# Sound.net
KiCad netlist of a schematic drawn in EAGLE
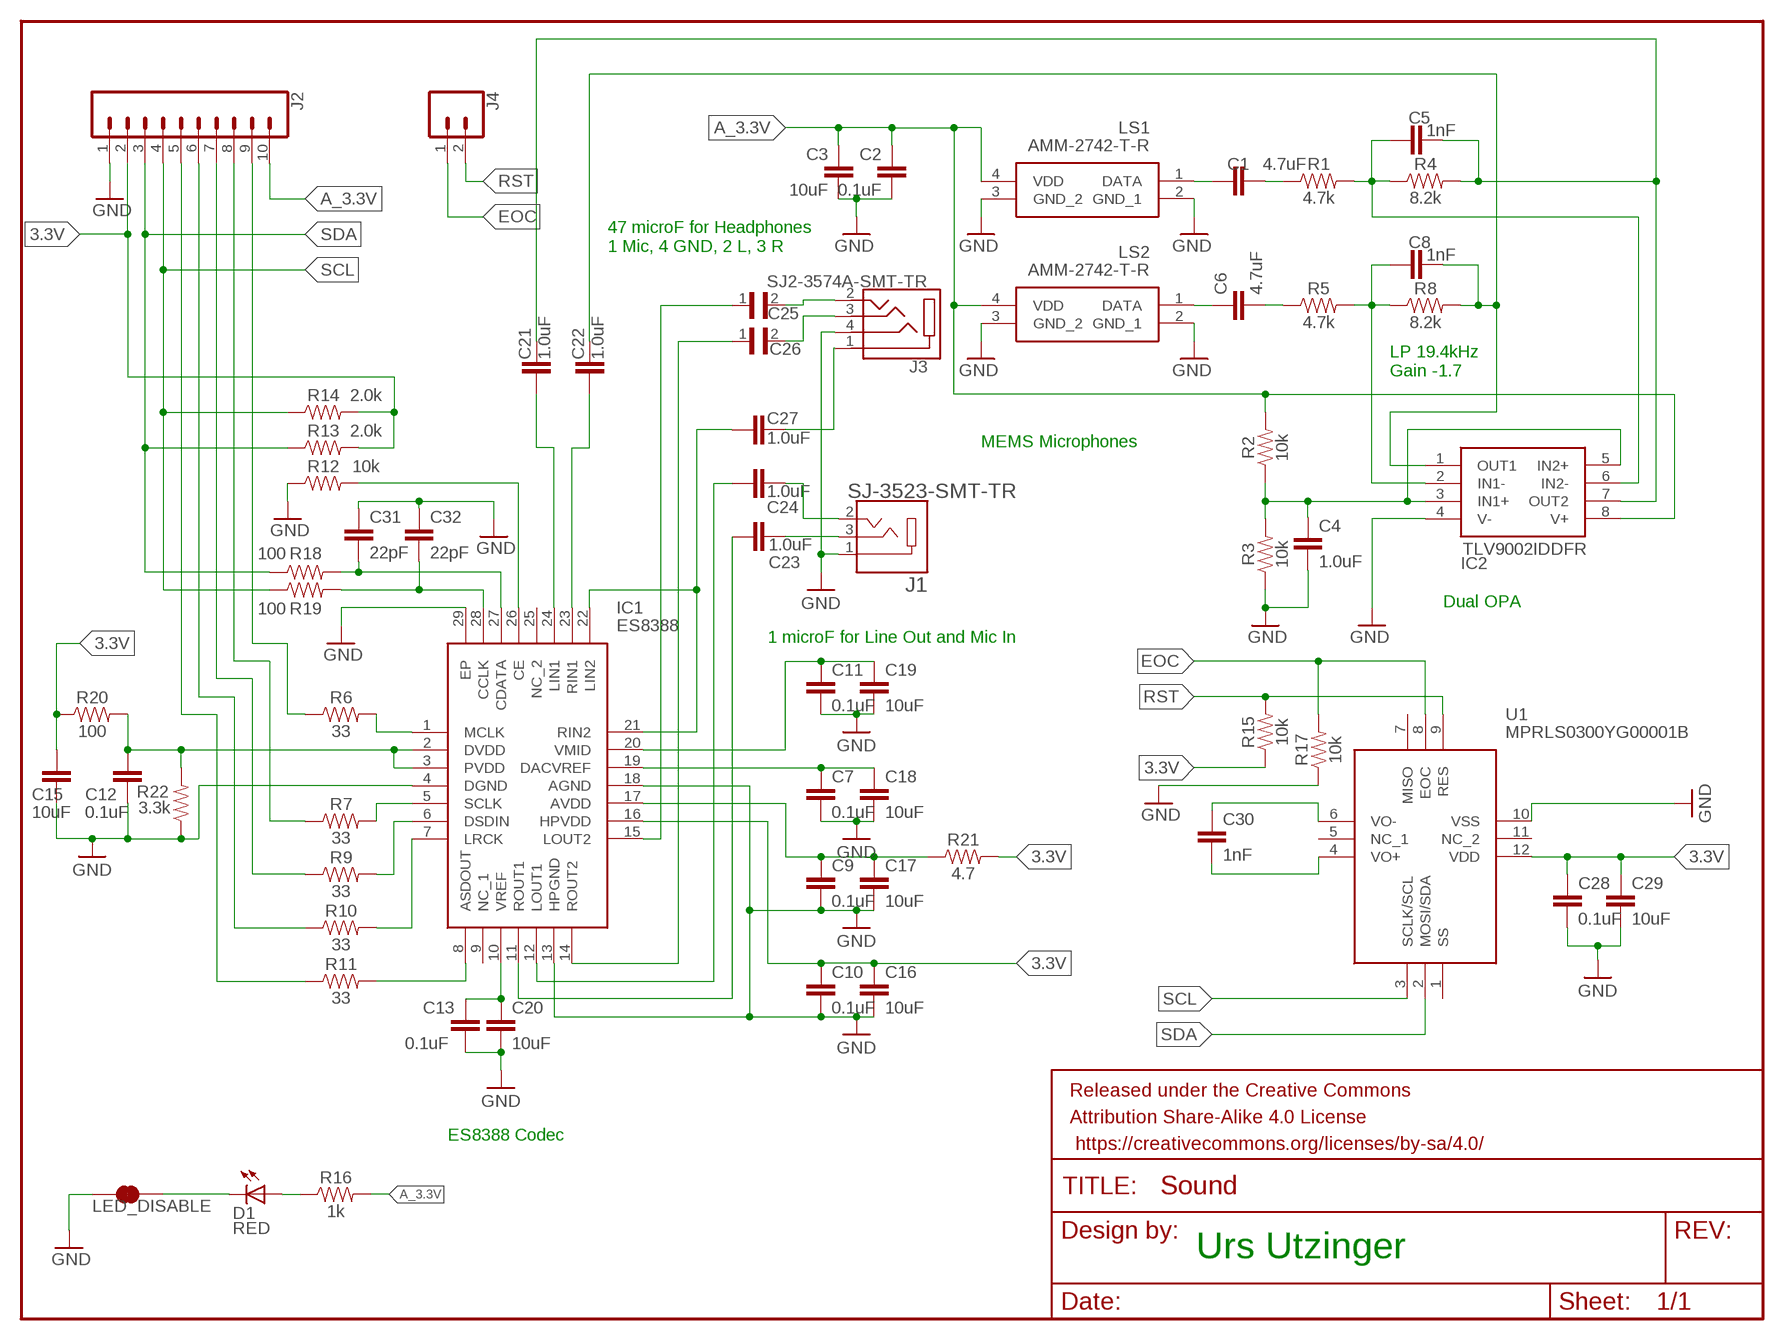
[diagram p0: schematic, sheet 1]

(export (version "E")
  (design (tool "Eeschema 10.0.6"))
  (components
    (comp (ref "C1")
      (value "4.7uF")
      (footprint "eagle-import:0603")
      (libsource (lib "eagle-import") (part "4.7UF-0603-6.3V-(10%)"))
    )
    (comp (ref "C2")
      (value "0.1uF")
      (footprint "eagle-import:0603")
      (libsource (lib "eagle-import") (part "0.1UF-0603-25V-5%"))
    )
    (comp (ref "C3")
      (value "10uF")
      (footprint "eagle-import:0603")
      (libsource (lib "eagle-import") (part "10UF-0603-6.3V-20%"))
    )
    (comp (ref "C4")
      (value "1.0uF")
      (footprint "eagle-import:0603")
      (libsource (lib "eagle-import") (part "1.0UF-0603-16V-10%"))
    )
    (comp (ref "C5")
      (value "1nF")
      (footprint "eagle-import:0603")
      (libsource (lib "eagle-import") (part "1.0NF/1000PF-0603-50V-10%"))
    )
    (comp (ref "C6")
      (value "4.7uF")
      (footprint "eagle-import:0603")
      (libsource (lib "eagle-import") (part "4.7UF-0603-6.3V-(10%)"))
    )
    (comp (ref "C7")
      (value "0.1uF")
      (footprint "eagle-import:0603")
      (libsource (lib "eagle-import") (part "0.1UF-0603-25V-5%"))
    )
    (comp (ref "C8")
      (value "1nF")
      (footprint "eagle-import:0603")
      (libsource (lib "eagle-import") (part "1.0NF/1000PF-0603-50V-10%"))
    )
    (comp (ref "C9")
      (value "0.1uF")
      (footprint "eagle-import:0603")
      (libsource (lib "eagle-import") (part "0.1UF-0603-25V-5%"))
    )
    (comp (ref "C10")
      (value "0.1uF")
      (footprint "eagle-import:0603")
      (libsource (lib "eagle-import") (part "0.1UF-0603-25V-5%"))
    )
    (comp (ref "C11")
      (value "0.1uF")
      (footprint "eagle-import:0603")
      (libsource (lib "eagle-import") (part "0.1UF-0603-25V-5%"))
    )
    (comp (ref "C12")
      (value "0.1uF")
      (footprint "eagle-import:0603")
      (libsource (lib "eagle-import") (part "0.1UF-0603-25V-5%"))
    )
    (comp (ref "C13")
      (value "0.1uF")
      (footprint "eagle-import:0603")
      (libsource (lib "eagle-import") (part "0.1UF-0603-25V-5%"))
    )
    (comp (ref "C15")
      (value "10uF")
      (footprint "eagle-import:0603")
      (libsource (lib "eagle-import") (part "10UF-0603-6.3V-20%"))
    )
    (comp (ref "C16")
      (value "10uF")
      (footprint "eagle-import:0603")
      (libsource (lib "eagle-import") (part "10UF-0603-6.3V-20%"))
    )
    (comp (ref "C17")
      (value "10uF")
      (footprint "eagle-import:0603")
      (libsource (lib "eagle-import") (part "10UF-0603-6.3V-20%"))
    )
    (comp (ref "C18")
      (value "10uF")
      (footprint "eagle-import:0603")
      (libsource (lib "eagle-import") (part "10UF-0603-6.3V-20%"))
    )
    (comp (ref "C19")
      (value "10uF")
      (footprint "eagle-import:0603")
      (libsource (lib "eagle-import") (part "10UF-0603-6.3V-20%"))
    )
    (comp (ref "C20")
      (value "10uF")
      (footprint "eagle-import:0603")
      (libsource (lib "eagle-import") (part "10UF-0603-6.3V-20%"))
    )
    (comp (ref "C21")
      (value "1.0uF")
      (footprint "eagle-import:0603")
      (libsource (lib "eagle-import") (part "1.0UF-0603-16V-10%"))
    )
    (comp (ref "C22")
      (value "1.0uF")
      (footprint "eagle-import:0603")
      (libsource (lib "eagle-import") (part "1.0UF-0603-16V-10%"))
    )
    (comp (ref "C23")
      (value "1.0uF")
      (footprint "eagle-import:0603")
      (libsource (lib "eagle-import") (part "1.0UF-0603-16V-10%"))
    )
    (comp (ref "C24")
      (value "1.0uF")
      (footprint "eagle-import:0603")
      (libsource (lib "eagle-import") (part "1.0UF-0603-16V-10%"))
    )
    (comp (ref "C25")
      (value "GRM188R60J476ME15D")
      (footprint "eagle-import:CAPC1608X100N")
      (libsource (lib "eagle-import") (part "GRM188R60J476ME15D"))
    )
    (comp (ref "C26")
      (value "GRM188R60J476ME15D")
      (footprint "eagle-import:CAPC1608X100N")
      (libsource (lib "eagle-import") (part "GRM188R60J476ME15D"))
    )
    (comp (ref "C27")
      (value "1.0uF")
      (footprint "eagle-import:0603")
      (libsource (lib "eagle-import") (part "1.0UF-0603-16V-10%"))
    )
    (comp (ref "C28")
      (value "0.1uF")
      (footprint "eagle-import:0603")
      (libsource (lib "eagle-import") (part "0.1UF-0603-25V-5%"))
    )
    (comp (ref "C29")
      (value "10uF")
      (footprint "eagle-import:0603")
      (libsource (lib "eagle-import") (part "10UF-0603-6.3V-20%"))
    )
    (comp (ref "C30")
      (value "1nF")
      (footprint "eagle-import:0603")
      (libsource (lib "eagle-import") (part "1.0NF/1000PF-0603-50V-10%"))
    )
    (comp (ref "C31")
      (value "22pF")
      (footprint "eagle-import:0603")
      (libsource (lib "eagle-import") (part "22PF-0603-50V-5%"))
    )
    (comp (ref "C32")
      (value "22pF")
      (footprint "eagle-import:0603")
      (libsource (lib "eagle-import") (part "22PF-0603-50V-5%"))
    )
    (comp (ref "D1")
      (value "RED")
      (footprint "eagle-import:LED-0603")
      (libsource (lib "eagle-import") (part "LED-RED0603"))
    )
    (comp (ref "FRAME1")
      (value "FRAME-LETTERNO_PACKAGE")
      (footprint "eagle-import:DUMMY")
      (fields (field (name "DESIGNER") "Nobody"))
      (libsource (lib "eagle-import") (part "FRAME-LETTERNO_PACKAGE"))
    )
    (comp (ref "IC1")
      (value "ES8388")
      (footprint "eagle-import:QFN45P400X400X90-29N")
      (libsource (lib "eagle-import") (part "ES8388"))
    )
    (comp (ref "IC2")
      (value "TLV9002IDDFR")
      (footprint "eagle-import:SOT65P280X110-8N")
      (fields (field (name "MOUSER_PART_NUMBER") "595-TLV9002IDDFR"))
      (libsource (lib "eagle-import") (part "TLV9002IDDFR"))
    )
    (comp (ref "J1")
      (value "SJ-3523-SMT-TR")
      (footprint "eagle-import:CUI_SJ-3523-SMT-TR")
      (fields (field (name "MF") "CUI Inc"))
      (libsource (lib "eagle-import") (part "SJ-3523-SMT-TR"))
    )
    (comp (ref "J2")
      (value "CONN_10\"")
      (footprint "eagle-import:1X10")
      (libsource (lib "eagle-import") (part "CONN_10{dblquote}"))
    )
    (comp (ref "J3")
      (value "SJ2-3574A-SMT-TR")
      (footprint "eagle-import:CUI_SJ2-3574A-SMT-TR")
      (fields (field (name "MANUFACTURER") "CUI"))
      (libsource (lib "eagle-import") (part "SJ2-3574A-SMT-TR"))
    )
    (comp (ref "J4")
      (value "CONN_02")
      (footprint "eagle-import:1X02")
      (libsource (lib "eagle-import") (part "CONN_02"))
    )
    (comp (ref "LED_DISABLE")
      (value "JUMPER-SMT_2_NC_TRACE_SILK")
      (footprint "eagle-import:SMT-JUMPER_2_NC_TRACE_SILK")
      (libsource (lib "eagle-import") (part "JUMPER-SMT_2_NC_TRACE_SILK"))
    )
    (comp (ref "LS1")
      (value "AMM-2742-T-R")
      (footprint "eagle-import:AMM2742TR")
      (fields (field (name "MOUSER_PART_NUMBER") "665-AMM-2742-T-R"))
      (libsource (lib "eagle-import") (part "AMM-2742-T-R"))
    )
    (comp (ref "LS2")
      (value "AMM-2742-T-R")
      (footprint "eagle-import:AMM2742TR")
      (fields (field (name "MOUSER_PART_NUMBER") "665-AMM-2742-T-R"))
      (libsource (lib "eagle-import") (part "AMM-2742-T-R"))
    )
    (comp (ref "R1")
      (value "4.7k")
      (footprint "eagle-import:0603")
      (libsource (lib "eagle-import") (part "4.7KOHM-0603-1/10W-1%"))
    )
    (comp (ref "R2")
      (value "10k")
      (footprint "eagle-import:0603")
      (libsource (lib "eagle-import") (part "10KOHM-0603-1/10W-1%"))
    )
    (comp (ref "R3")
      (value "10k")
      (footprint "eagle-import:0603")
      (libsource (lib "eagle-import") (part "10KOHM-0603-1/10W-1%"))
    )
    (comp (ref "R4")
      (value "8.2k")
      (footprint "eagle-import:0603")
      (libsource (lib "eagle-import") (part "8.2KOHM-0603-1/10W-5%"))
    )
    (comp (ref "R5")
      (value "4.7k")
      (footprint "eagle-import:0603")
      (libsource (lib "eagle-import") (part "4.7KOHM-0603-1/10W-1%"))
    )
    (comp (ref "R6")
      (value "33")
      (footprint "eagle-import:0603")
      (libsource (lib "eagle-import") (part "33OHM-0603-1/10W-1%"))
    )
    (comp (ref "R7")
      (value "33")
      (footprint "eagle-import:0603")
      (libsource (lib "eagle-import") (part "33OHM-0603-1/10W-1%"))
    )
    (comp (ref "R8")
      (value "8.2k")
      (footprint "eagle-import:0603")
      (libsource (lib "eagle-import") (part "8.2KOHM-0603-1/10W-5%"))
    )
    (comp (ref "R9")
      (value "33")
      (footprint "eagle-import:0603")
      (libsource (lib "eagle-import") (part "33OHM-0603-1/10W-1%"))
    )
    (comp (ref "R10")
      (value "33")
      (footprint "eagle-import:0603")
      (libsource (lib "eagle-import") (part "33OHM-0603-1/10W-1%"))
    )
    (comp (ref "R11")
      (value "33")
      (footprint "eagle-import:0603")
      (libsource (lib "eagle-import") (part "33OHM-0603-1/10W-1%"))
    )
    (comp (ref "R12")
      (value "10k")
      (footprint "eagle-import:0603")
      (libsource (lib "eagle-import") (part "10KOHM-0603-1/10W-1%"))
    )
    (comp (ref "R13")
      (value "2.0k")
      (footprint "eagle-import:0603")
      (libsource (lib "eagle-import") (part "2.0KOHM-0603-1/10W-5%"))
    )
    (comp (ref "R14")
      (value "2.0k")
      (footprint "eagle-import:0603")
      (libsource (lib "eagle-import") (part "2.0KOHM-0603-1/10W-5%"))
    )
    (comp (ref "R15")
      (value "10k")
      (footprint "eagle-import:0603")
      (libsource (lib "eagle-import") (part "10KOHM-0603-1/10W-1%"))
    )
    (comp (ref "R16")
      (value "1k")
      (footprint "eagle-import:0603")
      (libsource (lib "eagle-import") (part "1KOHM-0603-1/10W-1%"))
    )
    (comp (ref "R17")
      (value "10k")
      (footprint "eagle-import:0603")
      (libsource (lib "eagle-import") (part "10KOHM-0603-1/10W-1%"))
    )
    (comp (ref "R18")
      (value "100")
      (footprint "eagle-import:0603")
      (libsource (lib "eagle-import") (part "100OHM-0603-1/10W-1%"))
    )
    (comp (ref "R19")
      (value "100")
      (footprint "eagle-import:0603")
      (libsource (lib "eagle-import") (part "100OHM-0603-1/10W-1%"))
    )
    (comp (ref "R20")
      (value "100")
      (footprint "eagle-import:0603")
      (libsource (lib "eagle-import") (part "100OHM-0603-1/10W-1%"))
    )
    (comp (ref "R21")
      (value "4.7")
      (footprint "eagle-import:0603")
      (libsource (lib "eagle-import") (part "4.7OHM-0603-1/10W-1%"))
    )
    (comp (ref "R22")
      (value "3.3k")
      (footprint "eagle-import:0603")
      (libsource (lib "eagle-import") (part "3.3KOHM-0603-1/10W-1%"))
    )
    (comp (ref "U1")
      (value "MPRLS0300YG00001B")
      (footprint "eagle-import:MPRLS0300YG00001B")
      (fields (field (name "MOUSER_PART_NUMBER") "785-MPRLS0300YG0001B"))
      (libsource (lib "eagle-import") (part "MPRLS0300YG00001B"))
    )
  )
  (nets
    (net (code "1") (name "3.3V") (class "Default")
      (node (ref "C10") (pin "1") (pinfunction "1_1") (pintype "passive"))
      (node (ref "C15") (pin "1") (pinfunction "1_1") (pintype "passive"))
      (node (ref "C16") (pin "1") (pinfunction "1_1") (pintype "passive"))
      (node (ref "C28") (pin "1") (pinfunction "1_1") (pintype "passive"))
      (node (ref "C29") (pin "1") (pinfunction "1_1") (pintype "passive"))
      (node (ref "IC1") (pin "16") (pinfunction "HPVDD_16") (pintype "bidirectional"))
      (node (ref "J2") (pin "2") (pinfunction "2_2") (pintype "passive"))
      (node (ref "R13") (pin "2") (pinfunction "2_2") (pintype "passive"))
      (node (ref "R14") (pin "2") (pinfunction "2_2") (pintype "passive"))
      (node (ref "R15") (pin "1") (pinfunction "1_1") (pintype "passive"))
      (node (ref "R20") (pin "1") (pinfunction "1_1") (pintype "passive"))
      (node (ref "R21") (pin "2") (pinfunction "2_2") (pintype "passive"))
      (node (ref "U1") (pin "12") (pinfunction "VDD_12") (pintype "bidirectional"))
    )
    (net (code "2") (name "A_3.3V") (class "Default")
      (node (ref "C2") (pin "1") (pinfunction "1_1") (pintype "passive"))
      (node (ref "C3") (pin "1") (pinfunction "1_1") (pintype "passive"))
      (node (ref "IC2") (pin "8") (pinfunction "V+_8") (pintype "bidirectional"))
      (node (ref "J2") (pin "10") (pinfunction "10_10") (pintype "passive"))
      (node (ref "LS1") (pin "4") (pinfunction "VDD_4") (pintype "bidirectional"))
      (node (ref "LS2") (pin "4") (pinfunction "VDD_4") (pintype "bidirectional"))
      (node (ref "R16") (pin "2") (pinfunction "2_2") (pintype "passive"))
      (node (ref "R2") (pin "2") (pinfunction "2_2") (pintype "passive"))
    )
    (net (code "3") (name "EOC") (class "Default")
      (node (ref "J4") (pin "1") (pinfunction "1_1") (pintype "passive"))
      (node (ref "R17") (pin "2") (pinfunction "2_2") (pintype "passive"))
      (node (ref "U1") (pin "8") (pinfunction "EOC_8") (pintype "bidirectional"))
    )
    (net (code "4") (name "GND") (class "Default")
      (node (ref "C10") (pin "2") (pinfunction "2_2") (pintype "passive"))
      (node (ref "C11") (pin "2") (pinfunction "2_2") (pintype "passive"))
      (node (ref "C12") (pin "2") (pinfunction "2_2") (pintype "passive"))
      (node (ref "C13") (pin "2") (pinfunction "2_2") (pintype "passive"))
      (node (ref "C15") (pin "2") (pinfunction "2_2") (pintype "passive"))
      (node (ref "C16") (pin "2") (pinfunction "2_2") (pintype "passive"))
      (node (ref "C17") (pin "2") (pinfunction "2_2") (pintype "passive"))
      (node (ref "C18") (pin "2") (pinfunction "2_2") (pintype "passive"))
      (node (ref "C19") (pin "2") (pinfunction "2_2") (pintype "passive"))
      (node (ref "C2") (pin "2") (pinfunction "2_2") (pintype "passive"))
      (node (ref "C20") (pin "2") (pinfunction "2_2") (pintype "passive"))
      (node (ref "C28") (pin "2") (pinfunction "2_2") (pintype "passive"))
      (node (ref "C29") (pin "2") (pinfunction "2_2") (pintype "passive"))
      (node (ref "C3") (pin "2") (pinfunction "2_2") (pintype "passive"))
      (node (ref "C31") (pin "1") (pinfunction "1_1") (pintype "passive"))
      (node (ref "C32") (pin "1") (pinfunction "1_1") (pintype "passive"))
      (node (ref "C4") (pin "2") (pinfunction "2_2") (pintype "passive"))
      (node (ref "C7") (pin "2") (pinfunction "2_2") (pintype "passive"))
      (node (ref "C9") (pin "2") (pinfunction "2_2") (pintype "passive"))
      (node (ref "IC1") (pin "13") (pinfunction "HPGND_13") (pintype "bidirectional"))
      (node (ref "IC1") (pin "18") (pinfunction "AGND_18") (pintype "bidirectional"))
      (node (ref "IC1") (pin "29") (pinfunction "EP_29") (pintype "bidirectional"))
      (node (ref "IC1") (pin "4") (pinfunction "DGND_4") (pintype "bidirectional"))
      (node (ref "IC2") (pin "4") (pinfunction "V-_4") (pintype "bidirectional"))
      (node (ref "J1") (pin "1") (pinfunction "1_1") (pintype "passive"))
      (node (ref "J2") (pin "1") (pinfunction "1_1") (pintype "passive"))
      (node (ref "J3") (pin "4") (pinfunction "4_4") (pintype "passive"))
      (node (ref "LED_DISABLE") (pin "1") (pinfunction "1_1") (pintype "passive"))
      (node (ref "LS1") (pin "2") (pinfunction "GND_1_2") (pintype "bidirectional"))
      (node (ref "LS1") (pin "3") (pinfunction "GND_2_3") (pintype "bidirectional"))
      (node (ref "LS2") (pin "2") (pinfunction "GND_1_2") (pintype "bidirectional"))
      (node (ref "LS2") (pin "3") (pinfunction "GND_2_3") (pintype "bidirectional"))
      (node (ref "R12") (pin "1") (pinfunction "1_1") (pintype "passive"))
      (node (ref "R17") (pin "1") (pinfunction "1_1") (pintype "passive"))
      (node (ref "R22") (pin "1") (pinfunction "1_1") (pintype "passive"))
      (node (ref "R3") (pin "1") (pinfunction "1_1") (pintype "passive"))
      (node (ref "U1") (pin "10") (pinfunction "VSS_10") (pintype "bidirectional"))
    )
    (net (code "5") (name "Net-(C1-Pad2)") (class "Default")
      (node (ref "C1") (pin "2") (pinfunction "2_2") (pintype "passive"))
      (node (ref "R1") (pin "1") (pinfunction "1_1") (pintype "passive"))
    )
    (net (code "6") (name "Net-(C6-Pad2)") (class "Default")
      (node (ref "C6") (pin "2") (pinfunction "2_2") (pintype "passive"))
      (node (ref "R5") (pin "1") (pinfunction "1_1") (pintype "passive"))
    )
    (net (code "7") (name "Net-(C23-Pad1)") (class "Default")
      (node (ref "C23") (pin "1") (pinfunction "1_1") (pintype "passive"))
      (node (ref "J1") (pin "3") (pinfunction "3_3") (pintype "passive"))
    )
    (net (code "8") (name "Net-(C24-Pad1)") (class "Default")
      (node (ref "C24") (pin "1") (pinfunction "1_1") (pintype "passive"))
      (node (ref "J1") (pin "2") (pinfunction "2_2") (pintype "passive"))
    )
    (net (code "9") (name "Net-(C25-Pad2)") (class "Default")
      (node (ref "C25") (pin "2") (pinfunction "2_2") (pintype "passive"))
      (node (ref "J3") (pin "2") (pinfunction "2_2") (pintype "passive"))
    )
    (net (code "10") (name "Net-(C26-Pad2)") (class "Default")
      (node (ref "C26") (pin "2") (pinfunction "2_2") (pintype "passive"))
      (node (ref "J3") (pin "3") (pinfunction "3_3") (pintype "passive"))
    )
    (net (code "11") (name "Net-(C27-Pad2)") (class "Default")
      (node (ref "C27") (pin "2") (pinfunction "2_2") (pintype "passive"))
      (node (ref "J3") (pin "1") (pinfunction "1_1") (pintype "passive"))
    )
    (net (code "12") (name "Net-(D1-PadA)") (class "Default")
      (node (ref "D1") (pin "A") (pinfunction "A_A") (pintype "passive"))
      (node (ref "R16") (pin "1") (pinfunction "1_1") (pintype "passive"))
    )
    (net (code "13") (name "Net-(D1-PadC)") (class "Default")
      (node (ref "D1") (pin "C") (pinfunction "C_C") (pintype "passive"))
      (node (ref "LED_DISABLE") (pin "2") (pinfunction "2_2") (pintype "passive"))
    )
    (net (code "14") (name "Net-(IC1-ASDOUT)") (class "Default")
      (node (ref "IC1") (pin "8") (pinfunction "ASDOUT_8") (pintype "bidirectional"))
      (node (ref "R11") (pin "2") (pinfunction "2_2") (pintype "passive"))
    )
    (net (code "15") (name "Net-(IC1-AVDD)") (class "Default")
      (node (ref "C17") (pin "1") (pinfunction "1_1") (pintype "passive"))
      (node (ref "C9") (pin "1") (pinfunction "1_1") (pintype "passive"))
      (node (ref "IC1") (pin "17") (pinfunction "AVDD_17") (pintype "bidirectional"))
      (node (ref "R21") (pin "1") (pinfunction "1_1") (pintype "passive"))
    )
    (net (code "16") (name "Net-(IC1-CCLK)") (class "Default")
      (node (ref "C32") (pin "2") (pinfunction "2_2") (pintype "passive"))
      (node (ref "IC1") (pin "28") (pinfunction "CCLK_28") (pintype "bidirectional"))
      (node (ref "R19") (pin "2") (pinfunction "2_2") (pintype "passive"))
    )
    (net (code "17") (name "Net-(IC1-CDATA)") (class "Default")
      (node (ref "C31") (pin "2") (pinfunction "2_2") (pintype "passive"))
      (node (ref "IC1") (pin "27") (pinfunction "CDATA_27") (pintype "bidirectional"))
      (node (ref "R18") (pin "2") (pinfunction "2_2") (pintype "passive"))
    )
    (net (code "18") (name "Net-(IC1-CE)") (class "Default")
      (node (ref "IC1") (pin "26") (pinfunction "CE_26") (pintype "bidirectional"))
      (node (ref "R12") (pin "2") (pinfunction "2_2") (pintype "passive"))
    )
    (net (code "19") (name "Net-(IC1-DACVREF)") (class "Default")
      (node (ref "C18") (pin "1") (pinfunction "1_1") (pintype "passive"))
      (node (ref "C7") (pin "1") (pinfunction "1_1") (pintype "passive"))
      (node (ref "IC1") (pin "19") (pinfunction "DACVREF_19") (pintype "bidirectional"))
    )
    (net (code "20") (name "Net-(IC1-DSDIN)") (class "Default")
      (node (ref "IC1") (pin "6") (pinfunction "DSDIN_6") (pintype "bidirectional"))
      (node (ref "R9") (pin "2") (pinfunction "2_2") (pintype "passive"))
    )
    (net (code "21") (name "Net-(IC1-DVDD)") (class "Default")
      (node (ref "C12") (pin "1") (pinfunction "1_1") (pintype "passive"))
      (node (ref "IC1") (pin "2") (pinfunction "DVDD_2") (pintype "bidirectional"))
      (node (ref "IC1") (pin "3") (pinfunction "PVDD_3") (pintype "bidirectional"))
      (node (ref "R20") (pin "2") (pinfunction "2_2") (pintype "passive"))
      (node (ref "R22") (pin "2") (pinfunction "2_2") (pintype "passive"))
    )
    (net (code "22") (name "Net-(IC1-LIN1)") (class "Default")
      (node (ref "C21") (pin "1") (pinfunction "1_1") (pintype "passive"))
      (node (ref "IC1") (pin "24") (pinfunction "LIN1_24") (pintype "bidirectional"))
    )
    (net (code "23") (name "Net-(IC1-LIN2)") (class "Default")
      (node (ref "C27") (pin "1") (pinfunction "1_1") (pintype "passive"))
      (node (ref "IC1") (pin "21") (pinfunction "RIN2_21") (pintype "bidirectional"))
      (node (ref "IC1") (pin "22") (pinfunction "LIN2_22") (pintype "bidirectional"))
    )
    (net (code "24") (name "Net-(IC1-LOUT1)") (class "Default")
      (node (ref "C24") (pin "2") (pinfunction "2_2") (pintype "passive"))
      (node (ref "IC1") (pin "12") (pinfunction "LOUT1_12") (pintype "bidirectional"))
    )
    (net (code "25") (name "Net-(IC1-LOUT2)") (class "Default")
      (node (ref "C25") (pin "1") (pinfunction "1_1") (pintype "passive"))
      (node (ref "IC1") (pin "15") (pinfunction "LOUT2_15") (pintype "bidirectional"))
    )
    (net (code "26") (name "Net-(IC1-LRCK)") (class "Default")
      (node (ref "IC1") (pin "7") (pinfunction "LRCK_7") (pintype "bidirectional"))
      (node (ref "R10") (pin "2") (pinfunction "2_2") (pintype "passive"))
    )
    (net (code "27") (name "Net-(IC1-MCLK)") (class "Default")
      (node (ref "IC1") (pin "1") (pinfunction "MCLK_1") (pintype "bidirectional"))
      (node (ref "R6") (pin "2") (pinfunction "2_2") (pintype "passive"))
    )
    (net (code "28") (name "Net-(IC1-RIN1)") (class "Default")
      (node (ref "C22") (pin "1") (pinfunction "1_1") (pintype "passive"))
      (node (ref "IC1") (pin "23") (pinfunction "RIN1_23") (pintype "bidirectional"))
    )
    (net (code "29") (name "Net-(IC1-ROUT1)") (class "Default")
      (node (ref "C23") (pin "2") (pinfunction "2_2") (pintype "passive"))
      (node (ref "IC1") (pin "11") (pinfunction "ROUT1_11") (pintype "bidirectional"))
    )
    (net (code "30") (name "Net-(IC1-ROUT2)") (class "Default")
      (node (ref "C26") (pin "1") (pinfunction "1_1") (pintype "passive"))
      (node (ref "IC1") (pin "14") (pinfunction "ROUT2_14") (pintype "bidirectional"))
    )
    (net (code "31") (name "Net-(IC1-SCLK)") (class "Default")
      (node (ref "IC1") (pin "5") (pinfunction "SCLK_5") (pintype "bidirectional"))
      (node (ref "R7") (pin "2") (pinfunction "2_2") (pintype "passive"))
    )
    (net (code "32") (name "Net-(IC1-VMID)") (class "Default")
      (node (ref "C11") (pin "1") (pinfunction "1_1") (pintype "passive"))
      (node (ref "C19") (pin "1") (pinfunction "1_1") (pintype "passive"))
      (node (ref "IC1") (pin "20") (pinfunction "VMID_20") (pintype "bidirectional"))
    )
    (net (code "33") (name "Net-(IC1-VREF)") (class "Default")
      (node (ref "C13") (pin "1") (pinfunction "1_1") (pintype "passive"))
      (node (ref "C20") (pin "1") (pinfunction "1_1") (pintype "passive"))
      (node (ref "IC1") (pin "10") (pinfunction "VREF_10") (pintype "bidirectional"))
    )
    (net (code "34") (name "Net-(IC2-IN1+)") (class "Default")
      (node (ref "C4") (pin "1") (pinfunction "1_1") (pintype "passive"))
      (node (ref "IC2") (pin "3") (pinfunction "IN1+_3") (pintype "bidirectional"))
      (node (ref "IC2") (pin "5") (pinfunction "IN2+_5") (pintype "bidirectional"))
      (node (ref "R2") (pin "1") (pinfunction "1_1") (pintype "passive"))
      (node (ref "R3") (pin "2") (pinfunction "2_2") (pintype "passive"))
    )
    (net (code "35") (name "Net-(IC2-IN1-)") (class "Default")
      (node (ref "C8") (pin "1") (pinfunction "1_1") (pintype "passive"))
      (node (ref "IC2") (pin "2") (pinfunction "IN1-_2") (pintype "bidirectional"))
      (node (ref "R5") (pin "2") (pinfunction "2_2") (pintype "passive"))
      (node (ref "R8") (pin "1") (pinfunction "1_1") (pintype "passive"))
    )
    (net (code "36") (name "Net-(IC2-IN2-)") (class "Default")
      (node (ref "C5") (pin "1") (pinfunction "1_1") (pintype "passive"))
      (node (ref "IC2") (pin "6") (pinfunction "IN2-_6") (pintype "bidirectional"))
      (node (ref "R1") (pin "2") (pinfunction "2_2") (pintype "passive"))
      (node (ref "R4") (pin "1") (pinfunction "1_1") (pintype "passive"))
    )
    (net (code "37") (name "Net-(IC2-OUT1)") (class "Default")
      (node (ref "C22") (pin "2") (pinfunction "2_2") (pintype "passive"))
      (node (ref "C8") (pin "2") (pinfunction "2_2") (pintype "passive"))
      (node (ref "IC2") (pin "1") (pinfunction "OUT1_1") (pintype "bidirectional"))
      (node (ref "R8") (pin "2") (pinfunction "2_2") (pintype "passive"))
    )
    (net (code "38") (name "Net-(IC2-OUT2)") (class "Default")
      (node (ref "C21") (pin "2") (pinfunction "2_2") (pintype "passive"))
      (node (ref "C5") (pin "2") (pinfunction "2_2") (pintype "passive"))
      (node (ref "IC2") (pin "7") (pinfunction "OUT2_7") (pintype "bidirectional"))
      (node (ref "R4") (pin "2") (pinfunction "2_2") (pintype "passive"))
    )
    (net (code "39") (name "Net-(J2-Pad5)") (class "Default")
      (node (ref "J2") (pin "5") (pinfunction "5_5") (pintype "passive"))
      (node (ref "R11") (pin "1") (pinfunction "1_1") (pintype "passive"))
    )
    (net (code "40") (name "Net-(J2-Pad6)") (class "Default")
      (node (ref "J2") (pin "6") (pinfunction "6_6") (pintype "passive"))
      (node (ref "R10") (pin "1") (pinfunction "1_1") (pintype "passive"))
    )
    (net (code "41") (name "Net-(J2-Pad7)") (class "Default")
      (node (ref "J2") (pin "7") (pinfunction "7_7") (pintype "passive"))
      (node (ref "R9") (pin "1") (pinfunction "1_1") (pintype "passive"))
    )
    (net (code "42") (name "Net-(J2-Pad8)") (class "Default")
      (node (ref "J2") (pin "8") (pinfunction "8_8") (pintype "passive"))
      (node (ref "R7") (pin "1") (pinfunction "1_1") (pintype "passive"))
    )
    (net (code "43") (name "Net-(J2-Pad9)") (class "Default")
      (node (ref "J2") (pin "9") (pinfunction "9_9") (pintype "passive"))
      (node (ref "R6") (pin "1") (pinfunction "1_1") (pintype "passive"))
    )
    (net (code "44") (name "Net-(LS1-DATA)") (class "Default")
      (node (ref "C1") (pin "1") (pinfunction "1_1") (pintype "passive"))
      (node (ref "LS1") (pin "1") (pinfunction "DATA_1") (pintype "bidirectional"))
    )
    (net (code "45") (name "Net-(LS2-DATA)") (class "Default")
      (node (ref "C6") (pin "1") (pinfunction "1_1") (pintype "passive"))
      (node (ref "LS2") (pin "1") (pinfunction "DATA_1") (pintype "bidirectional"))
    )
    (net (code "46") (name "Net-(U1-VO+)") (class "Default")
      (node (ref "C30") (pin "2") (pinfunction "2_2") (pintype "passive"))
      (node (ref "U1") (pin "4") (pinfunction "VO+_4") (pintype "bidirectional"))
    )
    (net (code "47") (name "Net-(U1-VO-)") (class "Default")
      (node (ref "C30") (pin "1") (pinfunction "1_1") (pintype "passive"))
      (node (ref "U1") (pin "6") (pinfunction "VO-_6") (pintype "bidirectional"))
    )
    (net (code "48") (name "RST") (class "Default")
      (node (ref "J4") (pin "2") (pinfunction "2_2") (pintype "passive"))
      (node (ref "R15") (pin "2") (pinfunction "2_2") (pintype "passive"))
      (node (ref "U1") (pin "9") (pinfunction "RES_9") (pintype "bidirectional"))
    )
    (net (code "49") (name "SCL") (class "Default")
      (node (ref "J2") (pin "4") (pinfunction "4_4") (pintype "passive"))
      (node (ref "R14") (pin "1") (pinfunction "1_1") (pintype "passive"))
      (node (ref "R19") (pin "1") (pinfunction "1_1") (pintype "passive"))
      (node (ref "U1") (pin "3") (pinfunction "SCLK/SCL_3") (pintype "bidirectional"))
    )
    (net (code "50") (name "SDA") (class "Default")
      (node (ref "J2") (pin "3") (pinfunction "3_3") (pintype "passive"))
      (node (ref "R13") (pin "1") (pinfunction "1_1") (pintype "passive"))
      (node (ref "R18") (pin "1") (pinfunction "1_1") (pintype "passive"))
      (node (ref "U1") (pin "2") (pinfunction "MOSI/SDA_2") (pintype "bidirectional"))
    )
    (net (code "51") (name "unconnected-(IC1-NC_1-Pad9)") (class "Default")
      (node (ref "IC1") (pin "9") (pinfunction "NC_1_9") (pintype "bidirectional"))
    )
    (net (code "52") (name "unconnected-(IC1-NC_2-Pad25)") (class "Default")
      (node (ref "IC1") (pin "25") (pinfunction "NC_2_25") (pintype "bidirectional"))
    )
    (net (code "53") (name "unconnected-(U1-MISO-Pad7)") (class "Default")
      (node (ref "U1") (pin "7") (pinfunction "MISO_7") (pintype "bidirectional"))
    )
    (net (code "54") (name "unconnected-(U1-NC_1-Pad5)") (class "Default")
      (node (ref "U1") (pin "5") (pinfunction "NC_1_5") (pintype "bidirectional"))
    )
    (net (code "55") (name "unconnected-(U1-NC_2-Pad11)") (class "Default")
      (node (ref "U1") (pin "11") (pinfunction "NC_2_11") (pintype "bidirectional"))
    )
    (net (code "56") (name "unconnected-(U1-SS-Pad1)") (class "Default")
      (node (ref "U1") (pin "1") (pinfunction "SS_1") (pintype "bidirectional"))
    )
  )
)
